# RGB_Sensor.net
KiCad netlist of a schematic drawn in EAGLE
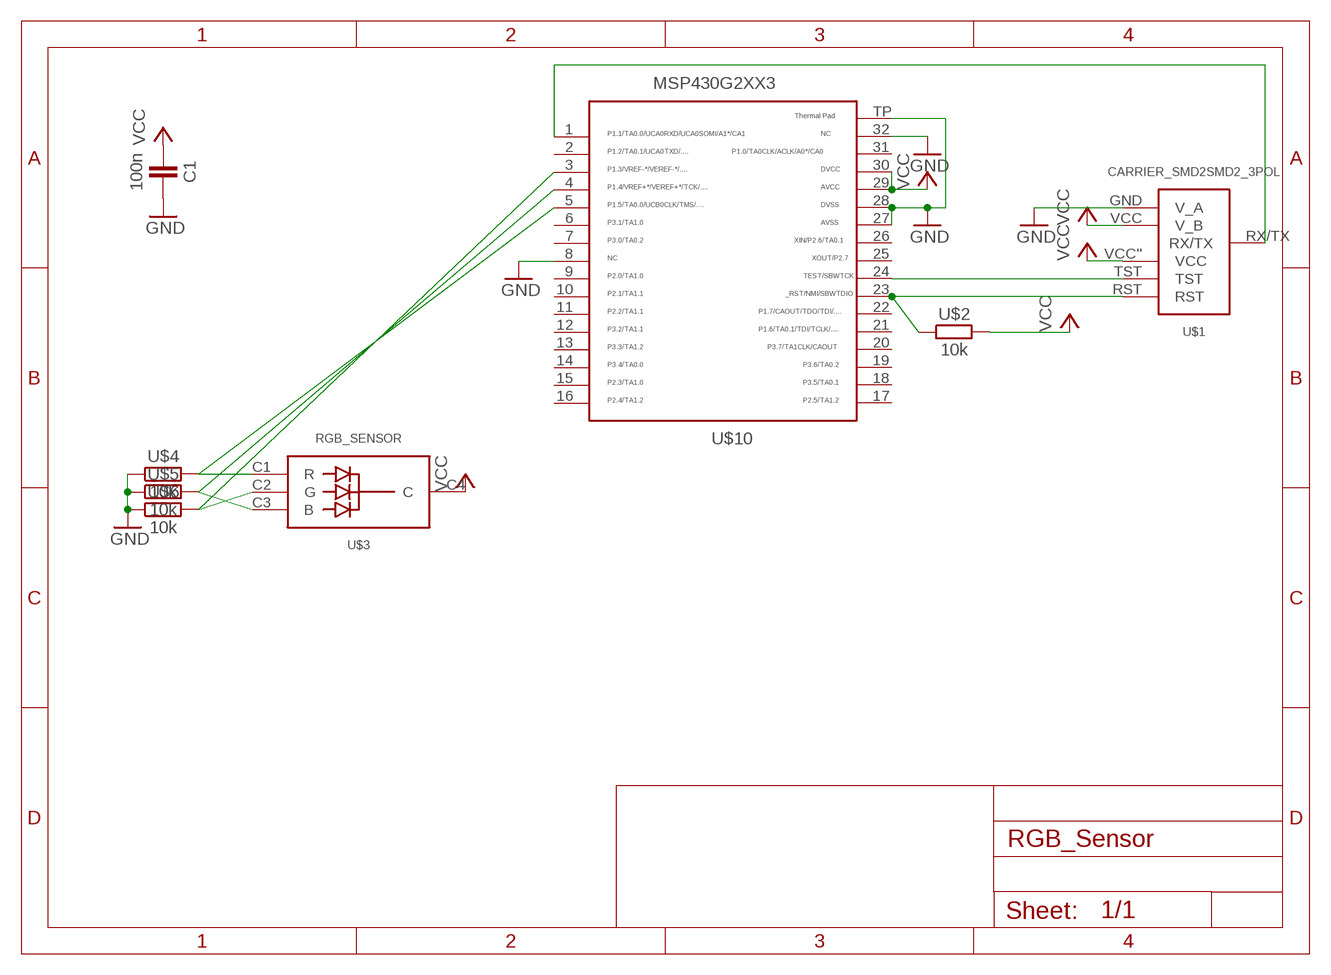
[diagram p0: schematic, sheet 1]

(export (version "E")
  (design (tool "Eeschema 10.0.6"))
  (components
    (comp (ref "C1")
      (value "100n")
      (footprint "eagle-import:603")
      (libsource (lib "eagle-import") (part "CAPACITOR"))
    )
    (comp (ref "U$1")
      (value "CARRIER_SMD2SMD2_3POL")
      (footprint "eagle-import:CARRIER_SMD2_3POL")
      (libsource (lib "eagle-import") (part "CARRIER_SMD2SMD2_3POL"))
    )
    (comp (ref "U$2")
      (value "10k")
      (footprint "eagle-import:603")
      (libsource (lib "eagle-import") (part "RESISTOR0603"))
    )
    (comp (ref "U$3")
      (value "RGB_SENSOR")
      (footprint "eagle-import:RGB_SENSOR")
      (libsource (lib "eagle-import") (part "RGB_SENSOR"))
    )
    (comp (ref "U$4")
      (value "10k")
      (footprint "eagle-import:603")
      (libsource (lib "eagle-import") (part "RESISTOR0603"))
    )
    (comp (ref "U$5")
      (value "10k")
      (footprint "eagle-import:603")
      (libsource (lib "eagle-import") (part "RESISTOR0603"))
    )
    (comp (ref "U$6")
      (value "10k")
      (footprint "eagle-import:603")
      (libsource (lib "eagle-import") (part "RESISTOR0603"))
    )
    (comp (ref "U$10")
      (value "MSP430G2553")
      (footprint "eagle-import:QFN32")
      (libsource (lib "eagle-import") (part "MSP430G2553"))
    )
  )
  (nets
    (net (code "1") (name "GND") (class "Default")
      (node (ref "C1") (pin "2") (pinfunction "2_2") (pintype "passive"))
      (node (ref "U$1") (pin "GND") (pinfunction "V_A_GND") (pintype "bidirectional"))
      (node (ref "U$10") (pin "27") (pinfunction "27_27") (pintype "bidirectional"))
      (node (ref "U$10") (pin "28") (pinfunction "28_28") (pintype "bidirectional"))
      (node (ref "U$10") (pin "32") (pinfunction "32_32") (pintype "bidirectional"))
      (node (ref "U$10") (pin "8") (pinfunction "8_8") (pintype "bidirectional"))
      (node (ref "U$10") (pin "TP") (pinfunction "TP_TP") (pintype "bidirectional"))
      (node (ref "U$4") (pin "1") (pinfunction "1_1") (pintype "passive"))
      (node (ref "U$5") (pin "1") (pinfunction "1_1") (pintype "passive"))
      (node (ref "U$6") (pin "1") (pinfunction "1_1") (pintype "passive"))
    )
    (net (code "2") (name "Net-(U$1-PadRST)") (class "Default")
      (node (ref "U$1") (pin "RST") (pinfunction "RST_RST") (pintype "bidirectional"))
      (node (ref "U$10") (pin "23") (pinfunction "23_23") (pintype "bidirectional"))
      (node (ref "U$2") (pin "1") (pinfunction "1_1") (pintype "passive"))
    )
    (net (code "3") (name "Net-(U$1-PadRX{slash}TX)") (class "Default")
      (node (ref "U$1") (pin "RX/TX") (pinfunction "RX/TX_RX/TX") (pintype "bidirectional"))
      (node (ref "U$10") (pin "1") (pinfunction "1_1") (pintype "bidirectional"))
    )
    (net (code "4") (name "Net-(U$1-PadTST)") (class "Default")
      (node (ref "U$1") (pin "TST") (pinfunction "TST_TST") (pintype "bidirectional"))
      (node (ref "U$10") (pin "24") (pinfunction "24_24") (pintype "bidirectional"))
    )
    (net (code "5") (name "Net-(U$3-B)") (class "Default")
      (node (ref "U$10") (pin "4") (pinfunction "4_4") (pintype "bidirectional"))
      (node (ref "U$3") (pin "C3") (pinfunction "B_C3") (pintype "bidirectional"))
      (node (ref "U$5") (pin "2") (pinfunction "2_2") (pintype "passive"))
    )
    (net (code "6") (name "Net-(U$3-G)") (class "Default")
      (node (ref "U$10") (pin "3") (pinfunction "3_3") (pintype "bidirectional"))
      (node (ref "U$3") (pin "C2") (pinfunction "G_C2") (pintype "bidirectional"))
      (node (ref "U$6") (pin "2") (pinfunction "2_2") (pintype "passive"))
    )
    (net (code "7") (name "Net-(U$3-R)") (class "Default")
      (node (ref "U$10") (pin "5") (pinfunction "5_5") (pintype "bidirectional"))
      (node (ref "U$3") (pin "C1") (pinfunction "R_C1") (pintype "bidirectional"))
      (node (ref "U$4") (pin "2") (pinfunction "2_2") (pintype "passive"))
    )
    (net (code "8") (name "VCC") (class "Default")
      (node (ref "C1") (pin "1") (pinfunction "1_1") (pintype "passive"))
      (node (ref "U$1") (pin "VCC") (pinfunction "V_B_VCC") (pintype "bidirectional"))
      (node (ref "U$1") (pin "VCC''") (pinfunction "VCC_VCC''") (pintype "bidirectional"))
      (node (ref "U$10") (pin "29") (pinfunction "29_29") (pintype "bidirectional"))
      (node (ref "U$10") (pin "30") (pinfunction "30_30") (pintype "bidirectional"))
      (node (ref "U$2") (pin "2") (pinfunction "2_2") (pintype "passive"))
      (node (ref "U$3") (pin "C4") (pinfunction "C_C4") (pintype "bidirectional"))
    )
    (net (code "9") (name "unconnected-(U$10-Pad2)") (class "Default")
      (node (ref "U$10") (pin "2") (pinfunction "2_2") (pintype "bidirectional"))
    )
    (net (code "10") (name "unconnected-(U$10-Pad6)") (class "Default")
      (node (ref "U$10") (pin "6") (pinfunction "6_6") (pintype "bidirectional"))
    )
    (net (code "11") (name "unconnected-(U$10-Pad7)") (class "Default")
      (node (ref "U$10") (pin "7") (pinfunction "7_7") (pintype "bidirectional"))
    )
    (net (code "12") (name "unconnected-(U$10-Pad9)") (class "Default")
      (node (ref "U$10") (pin "9") (pinfunction "9_9") (pintype "bidirectional"))
    )
    (net (code "13") (name "unconnected-(U$10-Pad10)") (class "Default")
      (node (ref "U$10") (pin "10") (pinfunction "10_10") (pintype "bidirectional"))
    )
    (net (code "14") (name "unconnected-(U$10-Pad11)") (class "Default")
      (node (ref "U$10") (pin "11") (pinfunction "11_11") (pintype "bidirectional"))
    )
    (net (code "15") (name "unconnected-(U$10-Pad12)") (class "Default")
      (node (ref "U$10") (pin "12") (pinfunction "12_12") (pintype "bidirectional"))
    )
    (net (code "16") (name "unconnected-(U$10-Pad13)") (class "Default")
      (node (ref "U$10") (pin "13") (pinfunction "13_13") (pintype "bidirectional"))
    )
    (net (code "17") (name "unconnected-(U$10-Pad14)") (class "Default")
      (node (ref "U$10") (pin "14") (pinfunction "14_14") (pintype "bidirectional"))
    )
    (net (code "18") (name "unconnected-(U$10-Pad15)") (class "Default")
      (node (ref "U$10") (pin "15") (pinfunction "15_15") (pintype "bidirectional"))
    )
    (net (code "19") (name "unconnected-(U$10-Pad16)") (class "Default")
      (node (ref "U$10") (pin "16") (pinfunction "16_16") (pintype "bidirectional"))
    )
    (net (code "20") (name "unconnected-(U$10-Pad17)") (class "Default")
      (node (ref "U$10") (pin "17") (pinfunction "17_17") (pintype "bidirectional"))
    )
    (net (code "21") (name "unconnected-(U$10-Pad18)") (class "Default")
      (node (ref "U$10") (pin "18") (pinfunction "18_18") (pintype "bidirectional"))
    )
    (net (code "22") (name "unconnected-(U$10-Pad19)") (class "Default")
      (node (ref "U$10") (pin "19") (pinfunction "19_19") (pintype "bidirectional"))
    )
    (net (code "23") (name "unconnected-(U$10-Pad20)") (class "Default")
      (node (ref "U$10") (pin "20") (pinfunction "20_20") (pintype "bidirectional"))
    )
    (net (code "24") (name "unconnected-(U$10-Pad21)") (class "Default")
      (node (ref "U$10") (pin "21") (pinfunction "21_21") (pintype "bidirectional"))
    )
    (net (code "25") (name "unconnected-(U$10-Pad22)") (class "Default")
      (node (ref "U$10") (pin "22") (pinfunction "22_22") (pintype "bidirectional"))
    )
    (net (code "26") (name "unconnected-(U$10-Pad25)") (class "Default")
      (node (ref "U$10") (pin "25") (pinfunction "25_25") (pintype "bidirectional"))
    )
    (net (code "27") (name "unconnected-(U$10-Pad26)") (class "Default")
      (node (ref "U$10") (pin "26") (pinfunction "26_26") (pintype "bidirectional"))
    )
    (net (code "28") (name "unconnected-(U$10-Pad31)") (class "Default")
      (node (ref "U$10") (pin "31") (pinfunction "31_31") (pintype "bidirectional"))
    )
  )
)
